# a.net
KiCad netlist of a schematic drawn in EAGLE
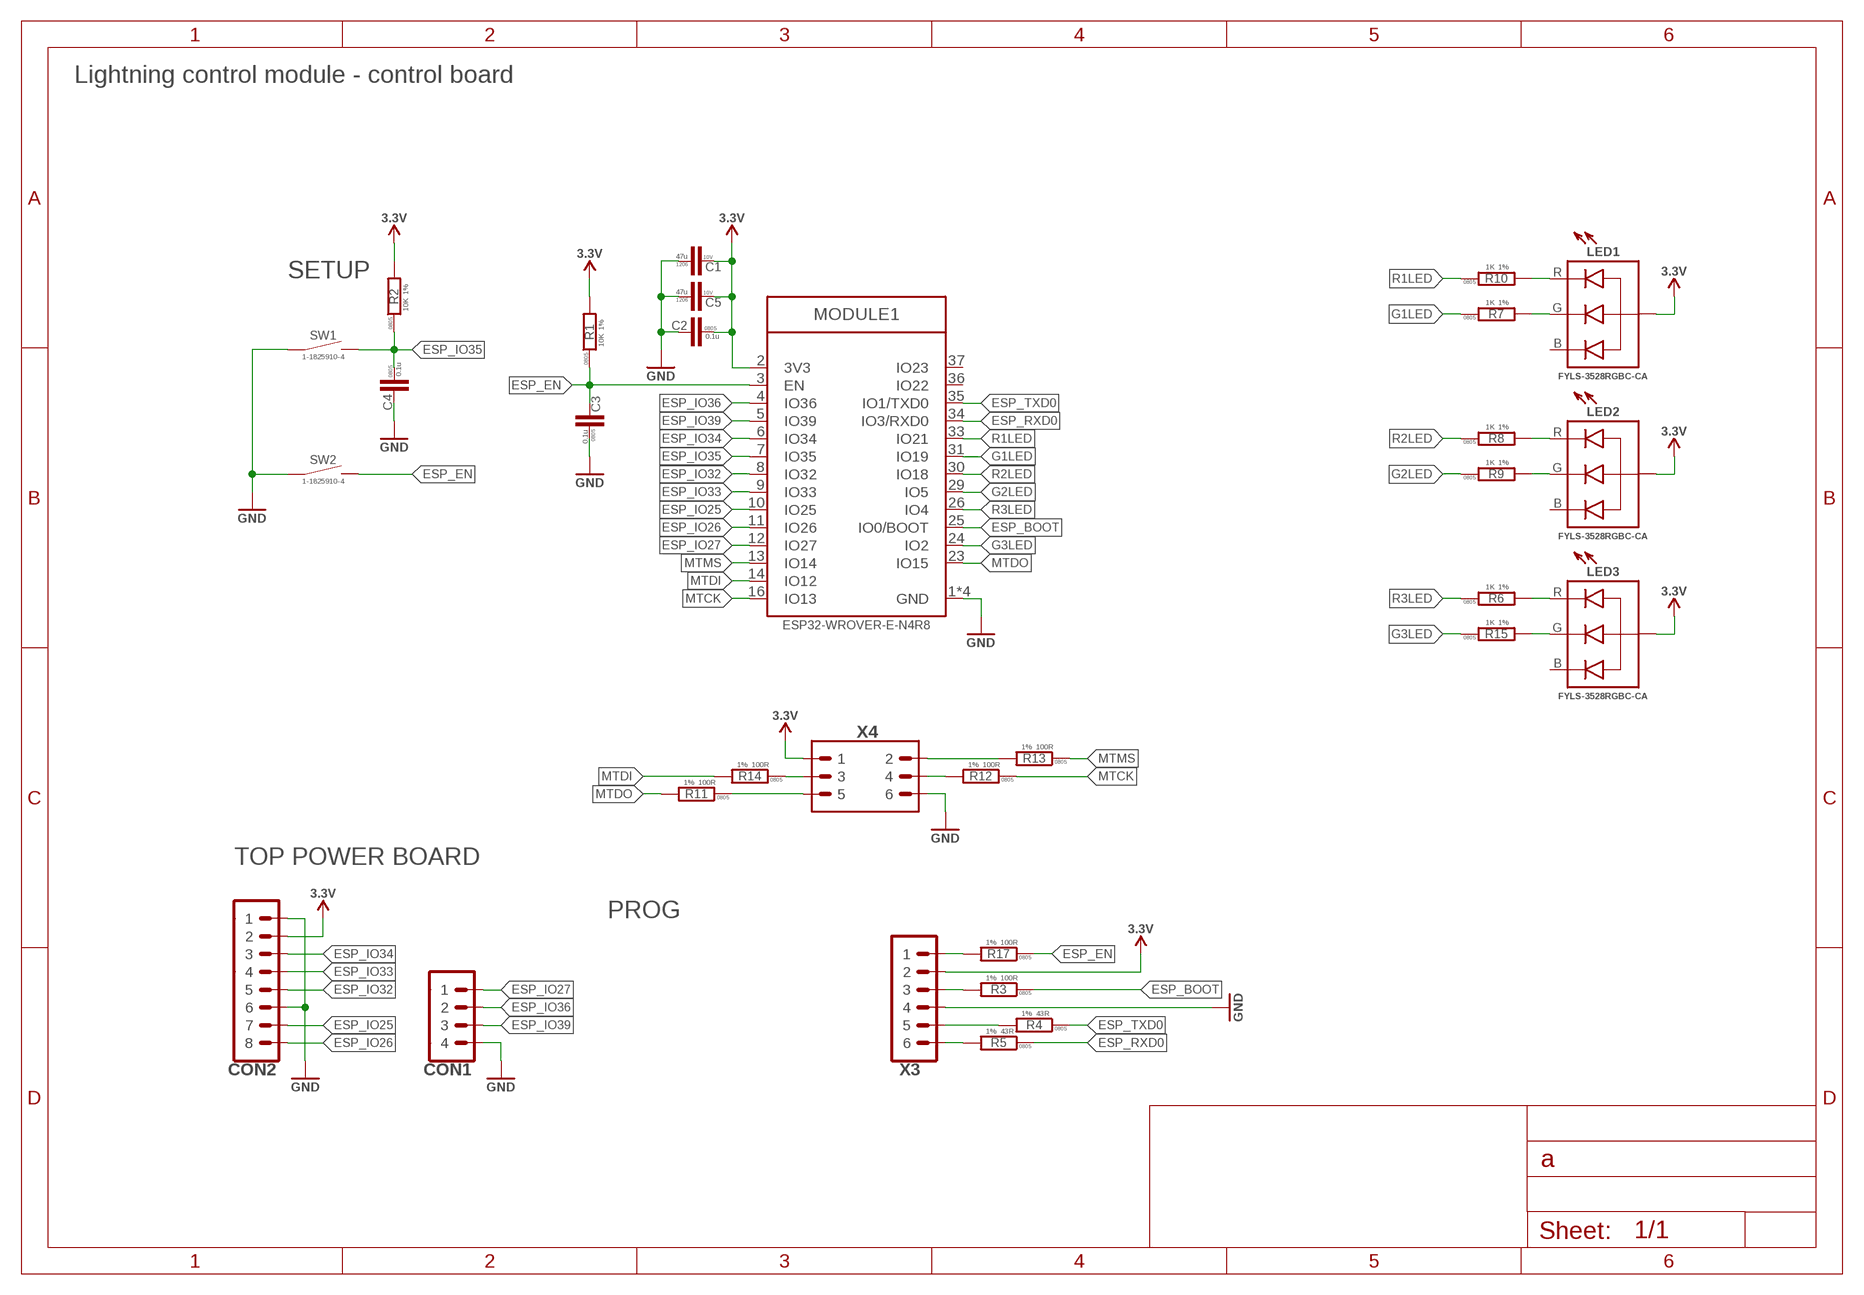
[diagram p0: schematic, sheet 1]

(export (version "E")
  (design (tool "Eeschema 10.0.6"))
  (components
    (comp (ref "C1")
      (value "47u")
      (footprint "eagle-import:C1206")
      (fields (field (name "PACKAGE") "1206") (field (name "VOLTAGE") "10V"))
      (libsource (lib "eagle-import") (part "C-1206"))
    )
    (comp (ref "C2")
      (value "0.1u")
      (footprint "eagle-import:C0805")
      (fields (field (name "PACKAGE") "0805"))
      (libsource (lib "eagle-import") (part "C-0805"))
    )
    (comp (ref "C3")
      (value "0.1u")
      (footprint "eagle-import:C0805")
      (fields (field (name "PACKAGE") "0805"))
      (libsource (lib "eagle-import") (part "C-0805"))
    )
    (comp (ref "C4")
      (value "0.1u")
      (footprint "eagle-import:C0805")
      (fields (field (name "PACKAGE") "0805"))
      (libsource (lib "eagle-import") (part "C-0805"))
    )
    (comp (ref "C5")
      (value "47u")
      (footprint "eagle-import:C1206")
      (fields (field (name "PACKAGE") "1206") (field (name "VOLTAGE") "10V"))
      (libsource (lib "eagle-import") (part "C-1206"))
    )
    (comp (ref "CON1")
      (value "PINHEAD_1X04-2.54")
      (footprint "eagle-import:1X04-PTH-2.54")
      (libsource (lib "eagle-import") (part "PINHEAD_1X04-2.54"))
    )
    (comp (ref "CON2")
      (value "PINHEAD_1X08-2.54")
      (footprint "eagle-import:1X08-PTH-2.54")
      (libsource (lib "eagle-import") (part "PINHEAD_1X08-2.54"))
    )
    (comp (ref "LED1")
      (value "LED_RGB-3528")
      (footprint "eagle-import:LED3528")
      (fields (field (name "MANF#") "FYLS-3528RGBC-CA") (field (name "MANF") "Foryard"))
      (libsource (lib "eagle-import") (part "LED_RGB-3528"))
    )
    (comp (ref "LED2")
      (value "LED_RGB-3528")
      (footprint "eagle-import:LED3528")
      (fields (field (name "MANF#") "FYLS-3528RGBC-CA") (field (name "MANF") "Foryard"))
      (libsource (lib "eagle-import") (part "LED_RGB-3528"))
    )
    (comp (ref "LED3")
      (value "LED_RGB-3528")
      (footprint "eagle-import:LED3528")
      (fields (field (name "MANF#") "FYLS-3528RGBC-CA") (field (name "MANF") "Foryard"))
      (libsource (lib "eagle-import") (part "LED_RGB-3528"))
    )
    (comp (ref "MODULE1")
      (value "ESP32-WROVER-(I)E")
      (footprint "eagle-import:ESP32-WROVER-E")
      (fields (field (name "MANF#") "ESP32-WROVER-E-N4R8") (field (name "MANF") "Espressif Systems"))
      (libsource (lib "eagle-import") (part "ESP32-WROVER-(I)E"))
    )
    (comp (ref "R1")
      (value "10K")
      (footprint "eagle-import:R0805")
      (fields (field (name "PACKAGE") "0805") (field (name "TOLERANCE") "1%"))
      (libsource (lib "eagle-import") (part "R-0805-1%"))
    )
    (comp (ref "R2")
      (value "10K")
      (footprint "eagle-import:R0805")
      (fields (field (name "PACKAGE") "0805") (field (name "TOLERANCE") "1%"))
      (libsource (lib "eagle-import") (part "R-0805-1%"))
    )
    (comp (ref "R3")
      (value "100R")
      (footprint "eagle-import:R0805")
      (fields (field (name "PACKAGE") "0805") (field (name "TOLERANCE") "1%"))
      (libsource (lib "eagle-import") (part "R-0805-1%"))
    )
    (comp (ref "R4")
      (value "43R")
      (footprint "eagle-import:R0805")
      (fields (field (name "PACKAGE") "0805") (field (name "TOLERANCE") "1%"))
      (libsource (lib "eagle-import") (part "R-0805-1%"))
    )
    (comp (ref "R5")
      (value "43R")
      (footprint "eagle-import:R0805")
      (fields (field (name "PACKAGE") "0805") (field (name "TOLERANCE") "1%"))
      (libsource (lib "eagle-import") (part "R-0805-1%"))
    )
    (comp (ref "R6")
      (value "1K")
      (footprint "eagle-import:R0805")
      (fields (field (name "PACKAGE") "0805") (field (name "TOLERANCE") "1%"))
      (libsource (lib "eagle-import") (part "R-0805-1%"))
    )
    (comp (ref "R7")
      (value "1K")
      (footprint "eagle-import:R0805")
      (fields (field (name "PACKAGE") "0805") (field (name "TOLERANCE") "1%"))
      (libsource (lib "eagle-import") (part "R-0805-1%"))
    )
    (comp (ref "R8")
      (value "1K")
      (footprint "eagle-import:R0805")
      (fields (field (name "PACKAGE") "0805") (field (name "TOLERANCE") "1%"))
      (libsource (lib "eagle-import") (part "R-0805-1%"))
    )
    (comp (ref "R9")
      (value "1K")
      (footprint "eagle-import:R0805")
      (fields (field (name "PACKAGE") "0805") (field (name "TOLERANCE") "1%"))
      (libsource (lib "eagle-import") (part "R-0805-1%"))
    )
    (comp (ref "R10")
      (value "1K")
      (footprint "eagle-import:R0805")
      (fields (field (name "PACKAGE") "0805") (field (name "TOLERANCE") "1%"))
      (libsource (lib "eagle-import") (part "R-0805-1%"))
    )
    (comp (ref "R11")
      (value "100R")
      (footprint "eagle-import:R0805")
      (fields (field (name "PACKAGE") "0805") (field (name "TOLERANCE") "1%"))
      (libsource (lib "eagle-import") (part "R-0805-1%"))
    )
    (comp (ref "R12")
      (value "100R")
      (footprint "eagle-import:R0805")
      (fields (field (name "PACKAGE") "0805") (field (name "TOLERANCE") "1%"))
      (libsource (lib "eagle-import") (part "R-0805-1%"))
    )
    (comp (ref "R13")
      (value "100R")
      (footprint "eagle-import:R0805")
      (fields (field (name "PACKAGE") "0805") (field (name "TOLERANCE") "1%"))
      (libsource (lib "eagle-import") (part "R-0805-1%"))
    )
    (comp (ref "R14")
      (value "100R")
      (footprint "eagle-import:R0805")
      (fields (field (name "PACKAGE") "0805") (field (name "TOLERANCE") "1%"))
      (libsource (lib "eagle-import") (part "R-0805-1%"))
    )
    (comp (ref "R15")
      (value "1K")
      (footprint "eagle-import:R0805")
      (fields (field (name "PACKAGE") "0805") (field (name "TOLERANCE") "1%"))
      (libsource (lib "eagle-import") (part "R-0805-1%"))
    )
    (comp (ref "R17")
      (value "100R")
      (footprint "eagle-import:R0805")
      (fields (field (name "PACKAGE") "0805") (field (name "TOLERANCE") "1%"))
      (libsource (lib "eagle-import") (part "R-0805-1%"))
    )
    (comp (ref "SW1")
      (value "TACT_SWITCH-1-1825910-4")
      (footprint "eagle-import:1-1825910-4")
      (fields (field (name "MANF") "TE Connectivity"))
      (libsource (lib "eagle-import") (part "TACT_SWITCH-1-1825910-4"))
    )
    (comp (ref "SW2")
      (value "TACT_SWITCH-1-1825910-4")
      (footprint "eagle-import:1-1825910-4")
      (fields (field (name "MANF") "TE Connectivity"))
      (libsource (lib "eagle-import") (part "TACT_SWITCH-1-1825910-4"))
    )
    (comp (ref "X3")
      (value "PINHEAD_1X06-2-MALE")
      (footprint "eagle-import:1X06-PTH-2")
      (libsource (lib "eagle-import") (part "PINHEAD_1X06-2-MALE"))
    )
    (comp (ref "X4")
      (value "PINHEAD_2X03-PTH-2.54")
      (footprint "eagle-import:2X03-PTH-2.54")
      (libsource (lib "eagle-import") (part "PINHEAD_2X03-PTH-2.54"))
    )
  )
  (nets
    (net (code "1") (name "3.3V") (class "Default")
      (node (ref "C1") (pin "P$2") (pinfunction "2_P$2") (pintype "passive"))
      (node (ref "C2") (pin "1") (pinfunction "1_1") (pintype "passive"))
      (node (ref "C5") (pin "P$2") (pinfunction "2_P$2") (pintype "passive"))
      (node (ref "CON2") (pin "2") (pinfunction "2_2") (pintype "passive"))
      (node (ref "LED1") (pin "2") (pinfunction "A_2") (pintype "bidirectional"))
      (node (ref "LED2") (pin "2") (pinfunction "A_2") (pintype "bidirectional"))
      (node (ref "LED3") (pin "2") (pinfunction "A_2") (pintype "bidirectional"))
      (node (ref "MODULE1") (pin "2") (pinfunction "3V3_2") (pintype "passive"))
      (node (ref "R1") (pin "2") (pinfunction "2_2") (pintype "passive"))
      (node (ref "R2") (pin "2") (pinfunction "2_2") (pintype "passive"))
      (node (ref "X3") (pin "2") (pinfunction "2_2") (pintype "passive"))
      (node (ref "X4") (pin "1") (pinfunction "1_1") (pintype "passive"))
    )
    (net (code "2") (name "ESP_BOOT") (class "Default")
      (node (ref "MODULE1") (pin "25") (pinfunction "IO0/BOOT_25") (pintype "tri_state"))
      (node (ref "R3") (pin "1") (pinfunction "1_1") (pintype "passive"))
    )
    (net (code "3") (name "ESP_EN") (class "Default")
      (node (ref "C3") (pin "2") (pinfunction "2_2") (pintype "passive"))
      (node (ref "MODULE1") (pin "3") (pinfunction "EN_3") (pintype "tri_state"))
      (node (ref "R1") (pin "1") (pinfunction "1_1") (pintype "passive"))
      (node (ref "R17") (pin "1") (pinfunction "1_1") (pintype "passive"))
      (node (ref "SW2") (pin "3") (pinfunction "2_3") (pintype "bidirectional"))
      (node (ref "SW2") (pin "4") (pinfunction "2_4") (pintype "bidirectional"))
    )
    (net (code "4") (name "ESP_IO25") (class "Default")
      (node (ref "CON2") (pin "7") (pinfunction "7_7") (pintype "passive"))
      (node (ref "MODULE1") (pin "10") (pinfunction "IO25_10") (pintype "tri_state"))
    )
    (net (code "5") (name "ESP_IO26") (class "Default")
      (node (ref "CON2") (pin "8") (pinfunction "8_8") (pintype "passive"))
      (node (ref "MODULE1") (pin "11") (pinfunction "IO26_11") (pintype "tri_state"))
    )
    (net (code "6") (name "ESP_IO27") (class "Default")
      (node (ref "CON1") (pin "1") (pinfunction "1_1") (pintype "passive"))
      (node (ref "MODULE1") (pin "12") (pinfunction "IO27_12") (pintype "tri_state"))
    )
    (net (code "7") (name "ESP_IO32") (class "Default")
      (node (ref "CON2") (pin "5") (pinfunction "5_5") (pintype "passive"))
      (node (ref "MODULE1") (pin "8") (pinfunction "IO32_8") (pintype "tri_state"))
    )
    (net (code "8") (name "ESP_IO33") (class "Default")
      (node (ref "CON2") (pin "4") (pinfunction "4_4") (pintype "passive"))
      (node (ref "MODULE1") (pin "9") (pinfunction "IO33_9") (pintype "tri_state"))
    )
    (net (code "9") (name "ESP_IO34") (class "Default")
      (node (ref "CON2") (pin "3") (pinfunction "3_3") (pintype "passive"))
      (node (ref "MODULE1") (pin "6") (pinfunction "IO34_6") (pintype "tri_state"))
    )
    (net (code "10") (name "ESP_IO35") (class "Default")
      (node (ref "C4") (pin "1") (pinfunction "1_1") (pintype "passive"))
      (node (ref "MODULE1") (pin "7") (pinfunction "IO35_7") (pintype "tri_state"))
      (node (ref "R2") (pin "1") (pinfunction "1_1") (pintype "passive"))
      (node (ref "SW1") (pin "3") (pinfunction "2_3") (pintype "bidirectional"))
      (node (ref "SW1") (pin "4") (pinfunction "2_4") (pintype "bidirectional"))
    )
    (net (code "11") (name "ESP_IO36") (class "Default")
      (node (ref "CON1") (pin "2") (pinfunction "2_2") (pintype "passive"))
      (node (ref "MODULE1") (pin "4") (pinfunction "IO36_4") (pintype "tri_state"))
    )
    (net (code "12") (name "ESP_IO39") (class "Default")
      (node (ref "CON1") (pin "3") (pinfunction "3_3") (pintype "passive"))
      (node (ref "MODULE1") (pin "5") (pinfunction "IO39_5") (pintype "tri_state"))
    )
    (net (code "13") (name "ESP_RXD0") (class "Default")
      (node (ref "MODULE1") (pin "34") (pinfunction "IO3/RXD0_34") (pintype "tri_state"))
      (node (ref "R5") (pin "1") (pinfunction "1_1") (pintype "passive"))
    )
    (net (code "14") (name "ESP_TXD0") (class "Default")
      (node (ref "MODULE1") (pin "35") (pinfunction "IO1/TXD0_35") (pintype "tri_state"))
      (node (ref "R4") (pin "1") (pinfunction "1_1") (pintype "passive"))
    )
    (net (code "15") (name "G1LED") (class "Default")
      (node (ref "MODULE1") (pin "31") (pinfunction "IO19_31") (pintype "tri_state"))
      (node (ref "R7") (pin "1") (pinfunction "1_1") (pintype "passive"))
    )
    (net (code "16") (name "G2LED") (class "Default")
      (node (ref "MODULE1") (pin "29") (pinfunction "IO5_29") (pintype "tri_state"))
      (node (ref "R9") (pin "1") (pinfunction "1_1") (pintype "passive"))
    )
    (net (code "17") (name "G3LED") (class "Default")
      (node (ref "MODULE1") (pin "24") (pinfunction "IO2_24") (pintype "tri_state"))
      (node (ref "R15") (pin "1") (pinfunction "1_1") (pintype "passive"))
    )
    (net (code "18") (name "GND") (class "Default")
      (node (ref "C1") (pin "P$1") (pinfunction "1_P$1") (pintype "passive"))
      (node (ref "C2") (pin "2") (pinfunction "2_2") (pintype "passive"))
      (node (ref "C3") (pin "1") (pinfunction "1_1") (pintype "passive"))
      (node (ref "C4") (pin "2") (pinfunction "2_2") (pintype "passive"))
      (node (ref "C5") (pin "P$1") (pinfunction "1_P$1") (pintype "passive"))
      (node (ref "CON1") (pin "4") (pinfunction "4_4") (pintype "passive"))
      (node (ref "CON2") (pin "1") (pinfunction "1_1") (pintype "passive"))
      (node (ref "CON2") (pin "6") (pinfunction "6_6") (pintype "passive"))
      (node (ref "MODULE1") (pin "1") (pinfunction "GND_1") (pintype "tri_state"))
      (node (ref "MODULE1") (pin "15") (pinfunction "GND_15") (pintype "tri_state"))
      (node (ref "MODULE1") (pin "38") (pinfunction "GND_38") (pintype "tri_state"))
      (node (ref "MODULE1") (pin "39") (pinfunction "GND_39") (pintype "tri_state"))
      (node (ref "SW1") (pin "1") (pinfunction "1_1") (pintype "bidirectional"))
      (node (ref "SW1") (pin "2") (pinfunction "1_2") (pintype "bidirectional"))
      (node (ref "SW2") (pin "1") (pinfunction "1_1") (pintype "bidirectional"))
      (node (ref "SW2") (pin "2") (pinfunction "1_2") (pintype "bidirectional"))
      (node (ref "X3") (pin "4") (pinfunction "4_4") (pintype "passive"))
      (node (ref "X4") (pin "6") (pinfunction "6_6") (pintype "passive"))
    )
    (net (code "19") (name "MTCK") (class "Default")
      (node (ref "MODULE1") (pin "16") (pinfunction "IO13_16") (pintype "tri_state"))
      (node (ref "R12") (pin "1") (pinfunction "1_1") (pintype "passive"))
    )
    (net (code "20") (name "MTDI") (class "Default")
      (node (ref "MODULE1") (pin "14") (pinfunction "IO12_14") (pintype "tri_state"))
      (node (ref "R14") (pin "2") (pinfunction "2_2") (pintype "passive"))
    )
    (net (code "21") (name "MTDO") (class "Default")
      (node (ref "MODULE1") (pin "23") (pinfunction "IO15_23") (pintype "tri_state"))
      (node (ref "R11") (pin "2") (pinfunction "2_2") (pintype "passive"))
    )
    (net (code "22") (name "MTMS") (class "Default")
      (node (ref "MODULE1") (pin "13") (pinfunction "IO14_13") (pintype "tri_state"))
      (node (ref "R13") (pin "1") (pinfunction "1_1") (pintype "passive"))
    )
    (net (code "23") (name "Net-(LED1-G)") (class "Default")
      (node (ref "LED1") (pin "4") (pinfunction "G_4") (pintype "bidirectional"))
      (node (ref "R7") (pin "2") (pinfunction "2_2") (pintype "passive"))
    )
    (net (code "24") (name "Net-(LED1-R)") (class "Default")
      (node (ref "LED1") (pin "1") (pinfunction "R_1") (pintype "bidirectional"))
      (node (ref "R10") (pin "2") (pinfunction "2_2") (pintype "passive"))
    )
    (net (code "25") (name "Net-(LED2-G)") (class "Default")
      (node (ref "LED2") (pin "4") (pinfunction "G_4") (pintype "bidirectional"))
      (node (ref "R9") (pin "2") (pinfunction "2_2") (pintype "passive"))
    )
    (net (code "26") (name "Net-(LED2-R)") (class "Default")
      (node (ref "LED2") (pin "1") (pinfunction "R_1") (pintype "bidirectional"))
      (node (ref "R8") (pin "2") (pinfunction "2_2") (pintype "passive"))
    )
    (net (code "27") (name "Net-(LED3-G)") (class "Default")
      (node (ref "LED3") (pin "4") (pinfunction "G_4") (pintype "bidirectional"))
      (node (ref "R15") (pin "2") (pinfunction "2_2") (pintype "passive"))
    )
    (net (code "28") (name "Net-(LED3-R)") (class "Default")
      (node (ref "LED3") (pin "1") (pinfunction "R_1") (pintype "bidirectional"))
      (node (ref "R6") (pin "2") (pinfunction "2_2") (pintype "passive"))
    )
    (net (code "29") (name "Net-(R3-Pad2)") (class "Default")
      (node (ref "R3") (pin "2") (pinfunction "2_2") (pintype "passive"))
      (node (ref "X3") (pin "3") (pinfunction "3_3") (pintype "passive"))
    )
    (net (code "30") (name "Net-(R4-Pad2)") (class "Default")
      (node (ref "R4") (pin "2") (pinfunction "2_2") (pintype "passive"))
      (node (ref "X3") (pin "5") (pinfunction "5_5") (pintype "passive"))
    )
    (net (code "31") (name "Net-(R5-Pad2)") (class "Default")
      (node (ref "R5") (pin "2") (pinfunction "2_2") (pintype "passive"))
      (node (ref "X3") (pin "6") (pinfunction "6_6") (pintype "passive"))
    )
    (net (code "32") (name "Net-(R11-Pad1)") (class "Default")
      (node (ref "R11") (pin "1") (pinfunction "1_1") (pintype "passive"))
      (node (ref "X4") (pin "5") (pinfunction "5_5") (pintype "passive"))
    )
    (net (code "33") (name "Net-(R12-Pad2)") (class "Default")
      (node (ref "R12") (pin "2") (pinfunction "2_2") (pintype "passive"))
      (node (ref "X4") (pin "4") (pinfunction "4_4") (pintype "passive"))
    )
    (net (code "34") (name "Net-(R13-Pad2)") (class "Default")
      (node (ref "R13") (pin "2") (pinfunction "2_2") (pintype "passive"))
      (node (ref "X4") (pin "2") (pinfunction "2_2") (pintype "passive"))
    )
    (net (code "35") (name "Net-(R14-Pad1)") (class "Default")
      (node (ref "R14") (pin "1") (pinfunction "1_1") (pintype "passive"))
      (node (ref "X4") (pin "3") (pinfunction "3_3") (pintype "passive"))
    )
    (net (code "36") (name "Net-(R17-Pad2)") (class "Default")
      (node (ref "R17") (pin "2") (pinfunction "2_2") (pintype "passive"))
      (node (ref "X3") (pin "1") (pinfunction "1_1") (pintype "passive"))
    )
    (net (code "37") (name "R1LED") (class "Default")
      (node (ref "MODULE1") (pin "33") (pinfunction "IO21_33") (pintype "tri_state"))
      (node (ref "R10") (pin "1") (pinfunction "1_1") (pintype "passive"))
    )
    (net (code "38") (name "R2LED") (class "Default")
      (node (ref "MODULE1") (pin "30") (pinfunction "IO18_30") (pintype "tri_state"))
      (node (ref "R8") (pin "1") (pinfunction "1_1") (pintype "passive"))
    )
    (net (code "39") (name "R3LED") (class "Default")
      (node (ref "MODULE1") (pin "26") (pinfunction "IO4_26") (pintype "tri_state"))
      (node (ref "R6") (pin "1") (pinfunction "1_1") (pintype "passive"))
    )
    (net (code "40") (name "unconnected-(LED1-B-Pad3)") (class "Default")
      (node (ref "LED1") (pin "3") (pinfunction "B_3") (pintype "bidirectional"))
    )
    (net (code "41") (name "unconnected-(LED2-B-Pad3)") (class "Default")
      (node (ref "LED2") (pin "3") (pinfunction "B_3") (pintype "bidirectional"))
    )
    (net (code "42") (name "unconnected-(LED3-B-Pad3)") (class "Default")
      (node (ref "LED3") (pin "3") (pinfunction "B_3") (pintype "bidirectional"))
    )
    (net (code "43") (name "unconnected-(MODULE1-IO22-Pad36)") (class "Default")
      (node (ref "MODULE1") (pin "36") (pinfunction "IO22_36") (pintype "tri_state"))
    )
    (net (code "44") (name "unconnected-(MODULE1-IO23-Pad37)") (class "Default")
      (node (ref "MODULE1") (pin "37") (pinfunction "IO23_37") (pintype "tri_state"))
    )
  )
)
